# R121A.net
KiCad netlist of a schematic drawn in EAGLE
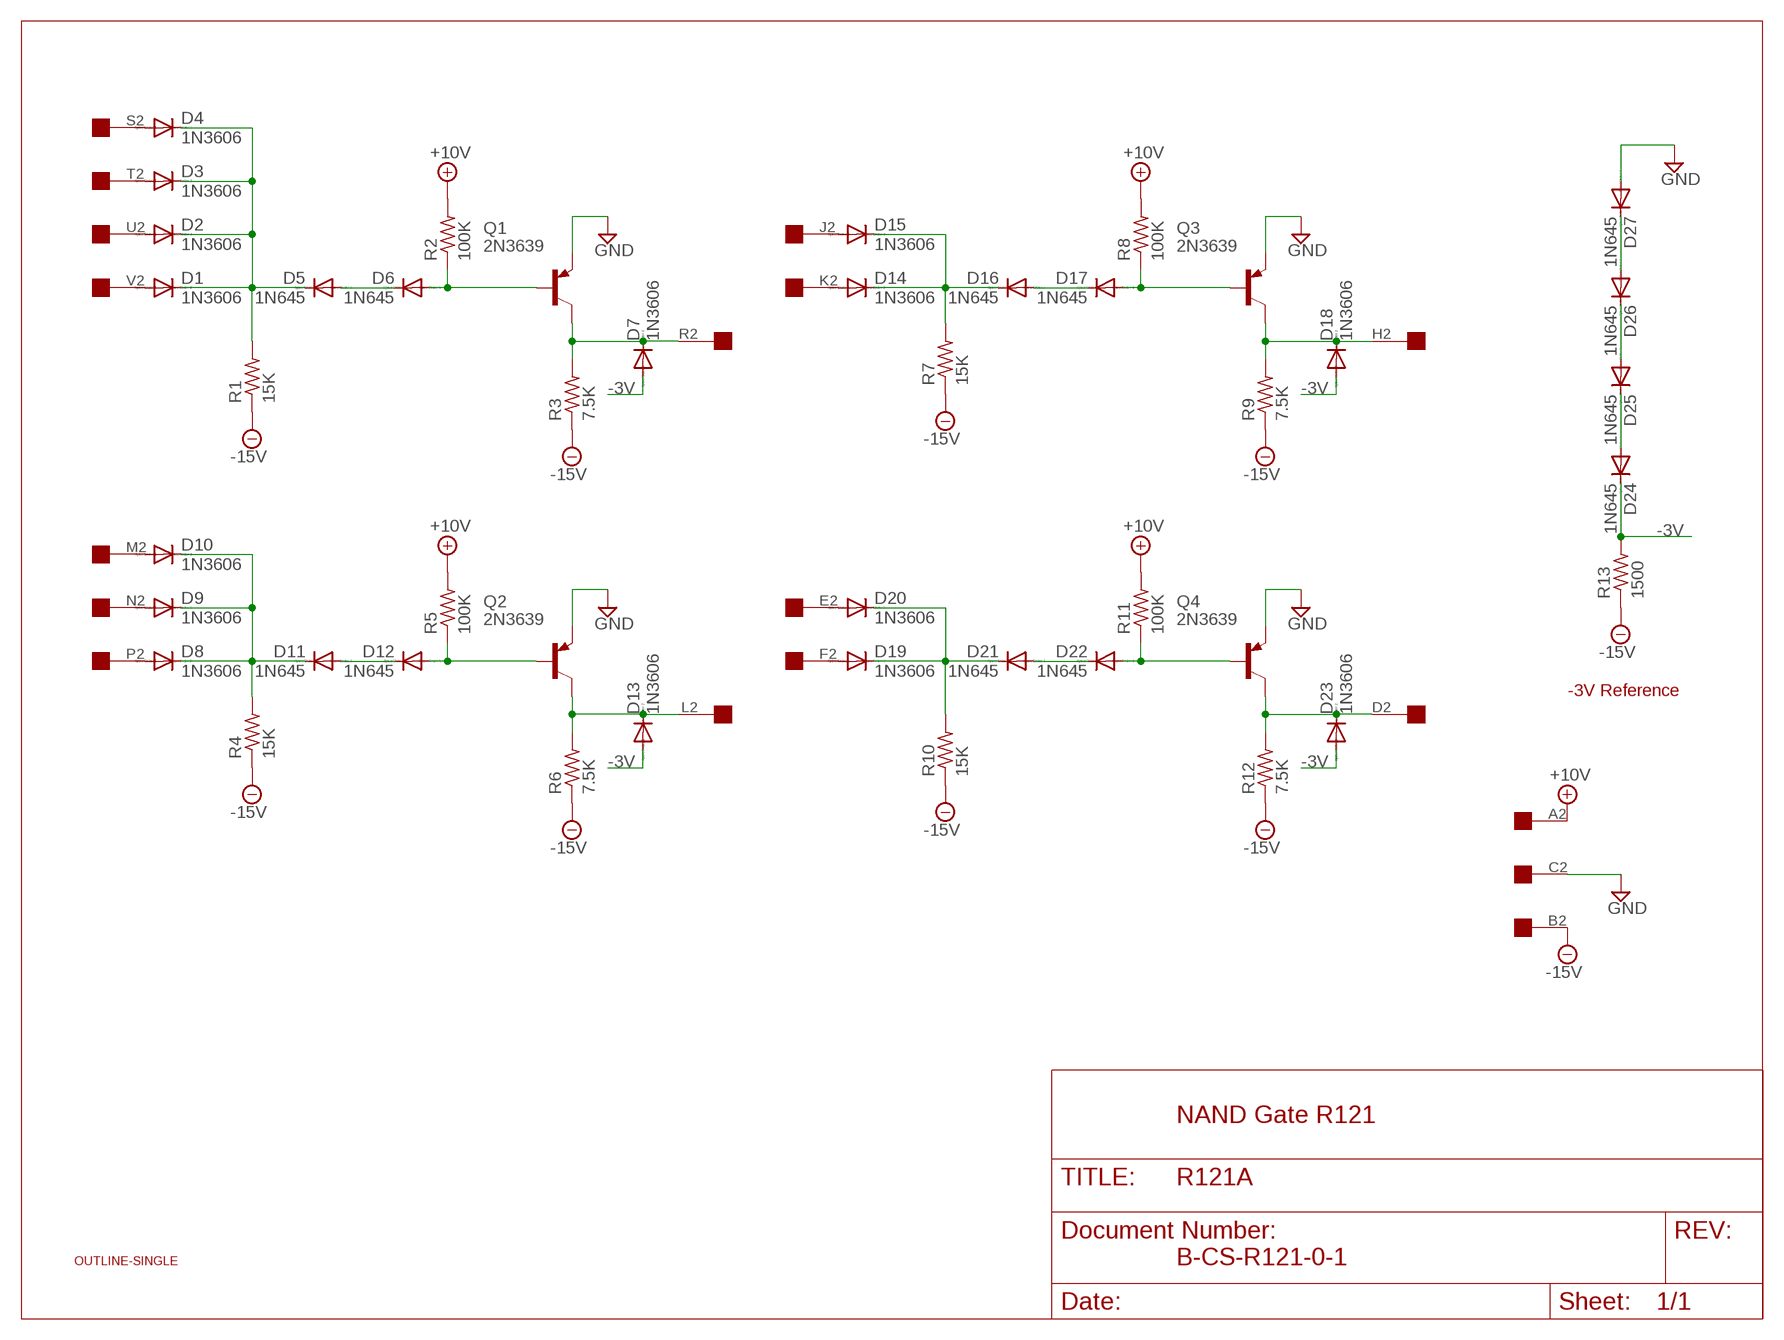
[diagram p0: schematic, sheet 1]

(export (version "E")
  (design (tool "Eeschema 10.0.6"))
  (components
    (comp (ref "D1")
      (value "1N3606")
      (footprint "eagle-import:DO35-10")
      (libsource (lib "eagle-import") (part "1N4148DO35-10"))
    )
    (comp (ref "D2")
      (value "1N3606")
      (footprint "eagle-import:DO35-10")
      (libsource (lib "eagle-import") (part "1N4148DO35-10"))
    )
    (comp (ref "D3")
      (value "1N3606")
      (footprint "eagle-import:DO35-10")
      (libsource (lib "eagle-import") (part "1N4148DO35-10"))
    )
    (comp (ref "D4")
      (value "1N3606")
      (footprint "eagle-import:DO35-10")
      (libsource (lib "eagle-import") (part "1N4148DO35-10"))
    )
    (comp (ref "D5")
      (value "1N645")
      (footprint "eagle-import:DO35-10")
      (libsource (lib "eagle-import") (part "1N4148DO35-10"))
    )
    (comp (ref "D6")
      (value "1N645")
      (footprint "eagle-import:DO35-10")
      (libsource (lib "eagle-import") (part "1N4148DO35-10"))
    )
    (comp (ref "D7")
      (value "1N3606")
      (footprint "eagle-import:DO35-10")
      (libsource (lib "eagle-import") (part "1N4148DO35-10"))
    )
    (comp (ref "D8")
      (value "1N3606")
      (footprint "eagle-import:DO35-10")
      (libsource (lib "eagle-import") (part "1N4148DO35-10"))
    )
    (comp (ref "D9")
      (value "1N3606")
      (footprint "eagle-import:DO35-10")
      (libsource (lib "eagle-import") (part "1N4148DO35-10"))
    )
    (comp (ref "D10")
      (value "1N3606")
      (footprint "eagle-import:DO35-10")
      (libsource (lib "eagle-import") (part "1N4148DO35-10"))
    )
    (comp (ref "D11")
      (value "1N645")
      (footprint "eagle-import:DO35-10")
      (libsource (lib "eagle-import") (part "1N4148DO35-10"))
    )
    (comp (ref "D12")
      (value "1N645")
      (footprint "eagle-import:DO35-10")
      (libsource (lib "eagle-import") (part "1N4148DO35-10"))
    )
    (comp (ref "D13")
      (value "1N3606")
      (footprint "eagle-import:DO35-10")
      (libsource (lib "eagle-import") (part "1N4148DO35-10"))
    )
    (comp (ref "D14")
      (value "1N3606")
      (footprint "eagle-import:DO35-10")
      (libsource (lib "eagle-import") (part "1N4148DO35-10"))
    )
    (comp (ref "D15")
      (value "1N3606")
      (footprint "eagle-import:DO35-10")
      (libsource (lib "eagle-import") (part "1N4148DO35-10"))
    )
    (comp (ref "D16")
      (value "1N645")
      (footprint "eagle-import:DO35-10")
      (libsource (lib "eagle-import") (part "1N4148DO35-10"))
    )
    (comp (ref "D17")
      (value "1N645")
      (footprint "eagle-import:DO35-10")
      (libsource (lib "eagle-import") (part "1N4148DO35-10"))
    )
    (comp (ref "D18")
      (value "1N3606")
      (footprint "eagle-import:DO35-10")
      (libsource (lib "eagle-import") (part "1N4148DO35-10"))
    )
    (comp (ref "D19")
      (value "1N3606")
      (footprint "eagle-import:DO35-10")
      (libsource (lib "eagle-import") (part "1N4148DO35-10"))
    )
    (comp (ref "D20")
      (value "1N3606")
      (footprint "eagle-import:DO35-10")
      (libsource (lib "eagle-import") (part "1N4148DO35-10"))
    )
    (comp (ref "D21")
      (value "1N645")
      (footprint "eagle-import:DO35-10")
      (libsource (lib "eagle-import") (part "1N4148DO35-10"))
    )
    (comp (ref "D22")
      (value "1N645")
      (footprint "eagle-import:DO35-10")
      (libsource (lib "eagle-import") (part "1N4148DO35-10"))
    )
    (comp (ref "D23")
      (value "1N3606")
      (footprint "eagle-import:DO35-10")
      (libsource (lib "eagle-import") (part "1N4148DO35-10"))
    )
    (comp (ref "D24")
      (value "1N645")
      (footprint "eagle-import:DO35-10")
      (libsource (lib "eagle-import") (part "1N4148DO35-10"))
    )
    (comp (ref "D25")
      (value "1N645")
      (footprint "eagle-import:DO35-10")
      (libsource (lib "eagle-import") (part "1N4148DO35-10"))
    )
    (comp (ref "D26")
      (value "1N645")
      (footprint "eagle-import:DO35-10")
      (libsource (lib "eagle-import") (part "1N4148DO35-10"))
    )
    (comp (ref "D27")
      (value "1N645")
      (footprint "eagle-import:DO35-10")
      (libsource (lib "eagle-import") (part "1N4148DO35-10"))
    )
    (comp (ref "Q1")
      (value "2N3639")
      (footprint "eagle-import:TO39")
      (libsource (lib "eagle-import") (part "2N3637"))
    )
    (comp (ref "Q2")
      (value "2N3639")
      (footprint "eagle-import:TO39")
      (libsource (lib "eagle-import") (part "2N3637"))
    )
    (comp (ref "Q3")
      (value "2N3639")
      (footprint "eagle-import:TO39")
      (libsource (lib "eagle-import") (part "2N3637"))
    )
    (comp (ref "Q4")
      (value "2N3639")
      (footprint "eagle-import:TO39")
      (libsource (lib "eagle-import") (part "2N3637"))
    )
    (comp (ref "R1")
      (value "15K")
      (footprint "eagle-import:0207_10")
      (libsource (lib "eagle-import") (part "R-US_0207/10"))
    )
    (comp (ref "R2")
      (value "100K")
      (footprint "eagle-import:0207_10")
      (libsource (lib "eagle-import") (part "R-US_0207/10"))
    )
    (comp (ref "R3")
      (value "7.5K")
      (footprint "eagle-import:0207_10")
      (libsource (lib "eagle-import") (part "R-US_0207/10"))
    )
    (comp (ref "R4")
      (value "15K")
      (footprint "eagle-import:0207_10")
      (libsource (lib "eagle-import") (part "R-US_0207/10"))
    )
    (comp (ref "R5")
      (value "100K")
      (footprint "eagle-import:0207_10")
      (libsource (lib "eagle-import") (part "R-US_0207/10"))
    )
    (comp (ref "R6")
      (value "7.5K")
      (footprint "eagle-import:0207_10")
      (libsource (lib "eagle-import") (part "R-US_0207/10"))
    )
    (comp (ref "R7")
      (value "15K")
      (footprint "eagle-import:0207_10")
      (libsource (lib "eagle-import") (part "R-US_0207/10"))
    )
    (comp (ref "R8")
      (value "100K")
      (footprint "eagle-import:0207_10")
      (libsource (lib "eagle-import") (part "R-US_0207/10"))
    )
    (comp (ref "R9")
      (value "7.5K")
      (footprint "eagle-import:0207_10")
      (libsource (lib "eagle-import") (part "R-US_0207/10"))
    )
    (comp (ref "R10")
      (value "15K")
      (footprint "eagle-import:0207_10")
      (libsource (lib "eagle-import") (part "R-US_0207/10"))
    )
    (comp (ref "R11")
      (value "100K")
      (footprint "eagle-import:0207_10")
      (libsource (lib "eagle-import") (part "R-US_0207/10"))
    )
    (comp (ref "R12")
      (value "7.5K")
      (footprint "eagle-import:0207_10")
      (libsource (lib "eagle-import") (part "R-US_0207/10"))
    )
    (comp (ref "R13")
      (value "1500")
      (footprint "eagle-import:0207_10")
      (libsource (lib "eagle-import") (part "R-US_0207/10"))
    )
    (comp (ref "U$1")
      (value "OUTLINE-SINGLE")
      (footprint "eagle-import:SINGLE")
      (libsource (lib "eagle-import") (part "OUTLINE-SINGLE"))
    )
    (comp (ref "U$2")
      (value "EDGE-1")
      (footprint "eagle-import:EDGE-CON1")
      (libsource (lib "eagle-import") (part "EDGE-1"))
    )
  )
  (nets
    (net (code "1") (name "+10V") (class "Default")
      (node (ref "R11") (pin "2") (pinfunction "2_2") (pintype "passive"))
      (node (ref "R2") (pin "2") (pinfunction "2_2") (pintype "passive"))
      (node (ref "R5") (pin "2") (pinfunction "2_2") (pintype "passive"))
      (node (ref "R8") (pin "2") (pinfunction "2_2") (pintype "passive"))
      (node (ref "U$2") (pin "A2") (pinfunction "1_A2") (pintype "bidirectional"))
    )
    (net (code "2") (name "-15V") (class "Default")
      (node (ref "R1") (pin "1") (pinfunction "1_1") (pintype "passive"))
      (node (ref "R10") (pin "1") (pinfunction "1_1") (pintype "passive"))
      (node (ref "R12") (pin "1") (pinfunction "1_1") (pintype "passive"))
      (node (ref "R13") (pin "1") (pinfunction "1_1") (pintype "passive"))
      (node (ref "R3") (pin "1") (pinfunction "1_1") (pintype "passive"))
      (node (ref "R4") (pin "1") (pinfunction "1_1") (pintype "passive"))
      (node (ref "R6") (pin "1") (pinfunction "1_1") (pintype "passive"))
      (node (ref "R7") (pin "1") (pinfunction "1_1") (pintype "passive"))
      (node (ref "R9") (pin "1") (pinfunction "1_1") (pintype "passive"))
      (node (ref "U$2") (pin "B2") (pinfunction "1_B2") (pintype "bidirectional"))
    )
    (net (code "3") (name "/-3V") (class "Default")
      (node (ref "D13") (pin "A") (pinfunction "A_A") (pintype "passive"))
      (node (ref "D18") (pin "A") (pinfunction "A_A") (pintype "passive"))
      (node (ref "D23") (pin "A") (pinfunction "A_A") (pintype "passive"))
      (node (ref "D24") (pin "C") (pinfunction "C_C") (pintype "passive"))
      (node (ref "D7") (pin "A") (pinfunction "A_A") (pintype "passive"))
      (node (ref "R13") (pin "2") (pinfunction "2_2") (pintype "passive"))
    )
    (net (code "4") (name "GND") (class "Default")
      (node (ref "D27") (pin "A") (pinfunction "A_A") (pintype "passive"))
      (node (ref "Q1") (pin "1") (pinfunction "E_1") (pintype "passive"))
      (node (ref "Q2") (pin "1") (pinfunction "E_1") (pintype "passive"))
      (node (ref "Q3") (pin "1") (pinfunction "E_1") (pintype "passive"))
      (node (ref "Q4") (pin "1") (pinfunction "E_1") (pintype "passive"))
      (node (ref "U$2") (pin "C2") (pinfunction "1_C2") (pintype "bidirectional"))
    )
    (net (code "5") (name "Net-(D1-PadC)") (class "Default")
      (node (ref "D1") (pin "C") (pinfunction "C_C") (pintype "passive"))
      (node (ref "D2") (pin "C") (pinfunction "C_C") (pintype "passive"))
      (node (ref "D3") (pin "C") (pinfunction "C_C") (pintype "passive"))
      (node (ref "D4") (pin "C") (pinfunction "C_C") (pintype "passive"))
      (node (ref "D5") (pin "C") (pinfunction "C_C") (pintype "passive"))
      (node (ref "R1") (pin "2") (pinfunction "2_2") (pintype "passive"))
    )
    (net (code "6") (name "Net-(D5-PadA)") (class "Default")
      (node (ref "D5") (pin "A") (pinfunction "A_A") (pintype "passive"))
      (node (ref "D6") (pin "C") (pinfunction "C_C") (pintype "passive"))
    )
    (net (code "7") (name "Net-(D10-PadC)") (class "Default")
      (node (ref "D10") (pin "C") (pinfunction "C_C") (pintype "passive"))
      (node (ref "D11") (pin "C") (pinfunction "C_C") (pintype "passive"))
      (node (ref "D8") (pin "C") (pinfunction "C_C") (pintype "passive"))
      (node (ref "D9") (pin "C") (pinfunction "C_C") (pintype "passive"))
      (node (ref "R4") (pin "2") (pinfunction "2_2") (pintype "passive"))
    )
    (net (code "8") (name "Net-(D11-PadA)") (class "Default")
      (node (ref "D11") (pin "A") (pinfunction "A_A") (pintype "passive"))
      (node (ref "D12") (pin "C") (pinfunction "C_C") (pintype "passive"))
    )
    (net (code "9") (name "Net-(D14-PadC)") (class "Default")
      (node (ref "D14") (pin "C") (pinfunction "C_C") (pintype "passive"))
      (node (ref "D15") (pin "C") (pinfunction "C_C") (pintype "passive"))
      (node (ref "D16") (pin "C") (pinfunction "C_C") (pintype "passive"))
      (node (ref "R7") (pin "2") (pinfunction "2_2") (pintype "passive"))
    )
    (net (code "10") (name "Net-(D16-PadA)") (class "Default")
      (node (ref "D16") (pin "A") (pinfunction "A_A") (pintype "passive"))
      (node (ref "D17") (pin "C") (pinfunction "C_C") (pintype "passive"))
    )
    (net (code "11") (name "Net-(D19-PadC)") (class "Default")
      (node (ref "D19") (pin "C") (pinfunction "C_C") (pintype "passive"))
      (node (ref "D20") (pin "C") (pinfunction "C_C") (pintype "passive"))
      (node (ref "D21") (pin "C") (pinfunction "C_C") (pintype "passive"))
      (node (ref "R10") (pin "2") (pinfunction "2_2") (pintype "passive"))
    )
    (net (code "12") (name "Net-(D21-PadA)") (class "Default")
      (node (ref "D21") (pin "A") (pinfunction "A_A") (pintype "passive"))
      (node (ref "D22") (pin "C") (pinfunction "C_C") (pintype "passive"))
    )
    (net (code "13") (name "Net-(D24-PadA)") (class "Default")
      (node (ref "D24") (pin "A") (pinfunction "A_A") (pintype "passive"))
      (node (ref "D25") (pin "C") (pinfunction "C_C") (pintype "passive"))
    )
    (net (code "14") (name "Net-(D25-PadA)") (class "Default")
      (node (ref "D25") (pin "A") (pinfunction "A_A") (pintype "passive"))
      (node (ref "D26") (pin "C") (pinfunction "C_C") (pintype "passive"))
    )
    (net (code "15") (name "Net-(D26-PadA)") (class "Default")
      (node (ref "D26") (pin "A") (pinfunction "A_A") (pintype "passive"))
      (node (ref "D27") (pin "C") (pinfunction "C_C") (pintype "passive"))
    )
    (net (code "16") (name "Net-(Q1-B)") (class "Default")
      (node (ref "D6") (pin "A") (pinfunction "A_A") (pintype "passive"))
      (node (ref "Q1") (pin "2") (pinfunction "B_2") (pintype "passive"))
      (node (ref "R2") (pin "1") (pinfunction "1_1") (pintype "passive"))
    )
    (net (code "17") (name "Net-(Q1-C)") (class "Default")
      (node (ref "D7") (pin "C") (pinfunction "C_C") (pintype "passive"))
      (node (ref "Q1") (pin "3") (pinfunction "C_3") (pintype "passive"))
      (node (ref "R3") (pin "2") (pinfunction "2_2") (pintype "passive"))
      (node (ref "U$2") (pin "R2") (pinfunction "1_R2") (pintype "bidirectional"))
    )
    (net (code "18") (name "Net-(Q2-B)") (class "Default")
      (node (ref "D12") (pin "A") (pinfunction "A_A") (pintype "passive"))
      (node (ref "Q2") (pin "2") (pinfunction "B_2") (pintype "passive"))
      (node (ref "R5") (pin "1") (pinfunction "1_1") (pintype "passive"))
    )
    (net (code "19") (name "Net-(Q2-C)") (class "Default")
      (node (ref "D13") (pin "C") (pinfunction "C_C") (pintype "passive"))
      (node (ref "Q2") (pin "3") (pinfunction "C_3") (pintype "passive"))
      (node (ref "R6") (pin "2") (pinfunction "2_2") (pintype "passive"))
      (node (ref "U$2") (pin "L2") (pinfunction "1_L2") (pintype "bidirectional"))
    )
    (net (code "20") (name "Net-(Q3-B)") (class "Default")
      (node (ref "D17") (pin "A") (pinfunction "A_A") (pintype "passive"))
      (node (ref "Q3") (pin "2") (pinfunction "B_2") (pintype "passive"))
      (node (ref "R8") (pin "1") (pinfunction "1_1") (pintype "passive"))
    )
    (net (code "21") (name "Net-(Q3-C)") (class "Default")
      (node (ref "D18") (pin "C") (pinfunction "C_C") (pintype "passive"))
      (node (ref "Q3") (pin "3") (pinfunction "C_3") (pintype "passive"))
      (node (ref "R9") (pin "2") (pinfunction "2_2") (pintype "passive"))
      (node (ref "U$2") (pin "H2") (pinfunction "1_H2") (pintype "bidirectional"))
    )
    (net (code "22") (name "Net-(Q4-B)") (class "Default")
      (node (ref "D22") (pin "A") (pinfunction "A_A") (pintype "passive"))
      (node (ref "Q4") (pin "2") (pinfunction "B_2") (pintype "passive"))
      (node (ref "R11") (pin "1") (pinfunction "1_1") (pintype "passive"))
    )
    (net (code "23") (name "Net-(Q4-C)") (class "Default")
      (node (ref "D23") (pin "C") (pinfunction "C_C") (pintype "passive"))
      (node (ref "Q4") (pin "3") (pinfunction "C_3") (pintype "passive"))
      (node (ref "R12") (pin "2") (pinfunction "2_2") (pintype "passive"))
      (node (ref "U$2") (pin "D2") (pinfunction "1_D2") (pintype "bidirectional"))
    )
    (net (code "24") (name "Net-(U$2E-1)") (class "Default")
      (node (ref "D20") (pin "A") (pinfunction "A_A") (pintype "passive"))
      (node (ref "U$2") (pin "E2") (pinfunction "1_E2") (pintype "bidirectional"))
    )
    (net (code "25") (name "Net-(U$2F-1)") (class "Default")
      (node (ref "D19") (pin "A") (pinfunction "A_A") (pintype "passive"))
      (node (ref "U$2") (pin "F2") (pinfunction "1_F2") (pintype "bidirectional"))
    )
    (net (code "26") (name "Net-(U$2H-1)") (class "Default")
      (node (ref "D15") (pin "A") (pinfunction "A_A") (pintype "passive"))
      (node (ref "U$2") (pin "J2") (pinfunction "1_J2") (pintype "bidirectional"))
    )
    (net (code "27") (name "Net-(U$2I-1)") (class "Default")
      (node (ref "D14") (pin "A") (pinfunction "A_A") (pintype "passive"))
      (node (ref "U$2") (pin "K2") (pinfunction "1_K2") (pintype "bidirectional"))
    )
    (net (code "28") (name "Net-(U$2K-1)") (class "Default")
      (node (ref "D10") (pin "A") (pinfunction "A_A") (pintype "passive"))
      (node (ref "U$2") (pin "M2") (pinfunction "1_M2") (pintype "bidirectional"))
    )
    (net (code "29") (name "Net-(U$2L-1)") (class "Default")
      (node (ref "D9") (pin "A") (pinfunction "A_A") (pintype "passive"))
      (node (ref "U$2") (pin "N2") (pinfunction "1_N2") (pintype "bidirectional"))
    )
    (net (code "30") (name "Net-(U$2M-1)") (class "Default")
      (node (ref "D8") (pin "A") (pinfunction "A_A") (pintype "passive"))
      (node (ref "U$2") (pin "P2") (pinfunction "1_P2") (pintype "bidirectional"))
    )
    (net (code "31") (name "Net-(U$2O-1)") (class "Default")
      (node (ref "D4") (pin "A") (pinfunction "A_A") (pintype "passive"))
      (node (ref "U$2") (pin "S2") (pinfunction "1_S2") (pintype "bidirectional"))
    )
    (net (code "32") (name "Net-(U$2P-1)") (class "Default")
      (node (ref "D3") (pin "A") (pinfunction "A_A") (pintype "passive"))
      (node (ref "U$2") (pin "T2") (pinfunction "1_T2") (pintype "bidirectional"))
    )
    (net (code "33") (name "Net-(U$2Q-1)") (class "Default")
      (node (ref "D2") (pin "A") (pinfunction "A_A") (pintype "passive"))
      (node (ref "U$2") (pin "U2") (pinfunction "1_U2") (pintype "bidirectional"))
    )
    (net (code "34") (name "Net-(U$2R-1)") (class "Default")
      (node (ref "D1") (pin "A") (pinfunction "A_A") (pintype "passive"))
      (node (ref "U$2") (pin "V2") (pinfunction "1_V2") (pintype "bidirectional"))
    )
  )
)
